# Sensors_Actuators.net
KiCad netlist of a schematic drawn in Altium Designer
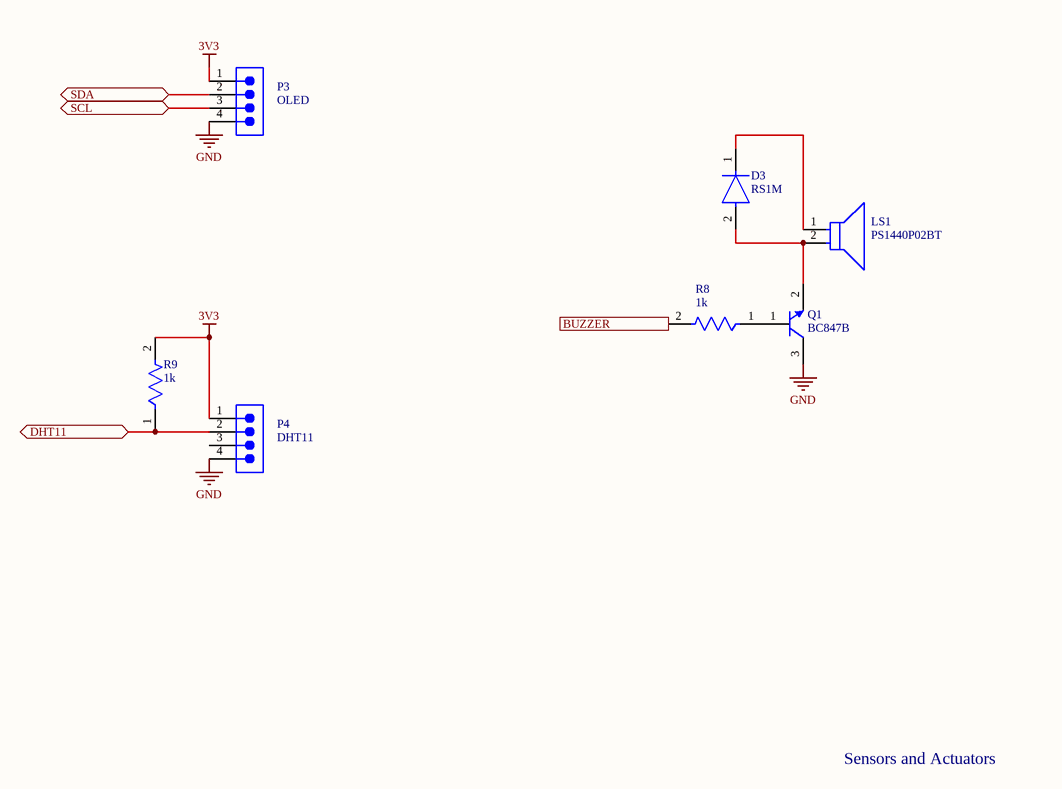
[diagram p0: Sensors_Actuators.SchDoc]

(export (version "E")
  (design (tool "Eeschema 10.0.6"))
  (components
    (comp (ref "D3")
      (value "RS1M")
      (footprint "FP-403AE-MFG")
      (description "DIODE GEN PURP 1KV 1A SMA")
      (fields
        (field (name "OCTOPART") "https://octopart.com/rs1m-on+semiconductor-84331238")
        (field (name "MANUFACTURER") "ON Semiconductor")
      )
      (libsource (lib "Altium Content Vault") (part "d7152d700b627762746794eb795d46e"))
    )
    (comp (ref "LS1")
      (value "PS1440P02BT")
      (footprint "FP-PS1440P02BT-MFG")
      (description "AUDIO PIEZO TRANSDUCER 30V TH")
      (libsource (lib "Altium Content Vault") (part "5f581d31613f872430949aa526fd155"))
    )
    (comp (ref "P3")
      (value "OLED")
      (footprint "61300411121")
      (libsource (lib "Altium Content Vault") (part "Header_Male_1R_04P"))
    )
    (comp (ref "P4")
      (value "DHT11")
      (footprint "61300411121")
      (libsource (lib "Altium Content Vault") (part "Header_Male_1R_04P"))
    )
    (comp (ref "Q1")
      (value "BC847B")
      (footprint "INF-SOT23_M")
      (description "NPN Silicon AF Transistor, 45 V VCEO, 100 mA IC, SOT23, Reel, Green")
      (fields (field (name "MANUFACTURER") "Infineon"))
      (libsource (lib "Altium Content Vault") (part "INF-BJTNPN-BEC-3"))
    )
    (comp (ref "R8")
      (value "1k")
      (footprint "FP-CRCW1206-e3-MFG")
      (description "RES Thick Film, 1.2kΩ, 1%, 0.25W, 100ppm/°C, 1206")
      (fields (field (name "TOLERANCE") "1%"))
      (libsource (lib "Altium Content Vault") (part "1029c3af85768c4190bb7ad29bc67b5"))
    )
    (comp (ref "R9")
      (value "1k")
      (footprint "FP-CRCW1206-e3-MFG")
      (description "RES Thick Film, 1.2kΩ, 1%, 0.25W, 100ppm/°C, 1206")
      (fields (field (name "TOLERANCE") "1%"))
      (libsource (lib "Altium Content Vault") (part "1029c3af85768c4190bb7ad29bc67b5"))
    )
  )
  (nets
    (net (code "1") (name "/BUZZER") (class "Default")
      (node (ref "R8") (pin "2") (pinfunction "2_2") (pintype "passive"))
    )
    (net (code "2") (name "/DHT11") (class "Default")
      (node (ref "P4") (pin "2") (pinfunction "2_2") (pintype "passive"))
      (node (ref "R9") (pin "1") (pinfunction "1_1") (pintype "passive"))
    )
    (net (code "3") (name "/SCL") (class "Default")
      (node (ref "P3") (pin "3") (pinfunction "3_3") (pintype "passive"))
    )
    (net (code "4") (name "/SDA") (class "Default")
      (node (ref "P3") (pin "2") (pinfunction "2_2") (pintype "passive"))
    )
    (net (code "5") (name "3V3") (class "Default")
      (node (ref "P3") (pin "1") (pinfunction "1_1") (pintype "passive"))
      (node (ref "P4") (pin "1") (pinfunction "1_1") (pintype "passive"))
      (node (ref "R9") (pin "2") (pinfunction "2_2") (pintype "passive"))
    )
    (net (code "6") (name "GND") (class "Default")
      (node (ref "P3") (pin "4") (pinfunction "4_4") (pintype "passive"))
      (node (ref "P4") (pin "4") (pinfunction "4_4") (pintype "passive"))
      (node (ref "Q1") (pin "3") (pinfunction "C_3") (pintype "passive"))
    )
    (net (code "7") (name "Net-(D3-A)") (class "Default")
      (node (ref "D3") (pin "2") (pinfunction "A_2") (pintype "passive"))
      (node (ref "LS1") (pin "2") (pinfunction "2_2") (pintype "passive"))
      (node (ref "Q1") (pin "2") (pinfunction "E_2") (pintype "passive"))
    )
    (net (code "8") (name "Net-(D3-C)") (class "Default")
      (node (ref "D3") (pin "1") (pinfunction "C_1") (pintype "passive"))
      (node (ref "LS1") (pin "1") (pinfunction "1_1") (pintype "passive"))
    )
    (net (code "9") (name "Net-(Q1-B)") (class "Default")
      (node (ref "Q1") (pin "1") (pinfunction "B_1") (pintype "passive"))
      (node (ref "R8") (pin "1") (pinfunction "1_1") (pintype "passive"))
    )
    (net (code "10") (name "unconnected-(P4-Pad3)") (class "Default")
      (node (ref "P4") (pin "3") (pinfunction "3_3") (pintype "passive"))
    )
  )
)
